# 2x8_GPIO_board.net
KiCad netlist of a schematic drawn in EAGLE
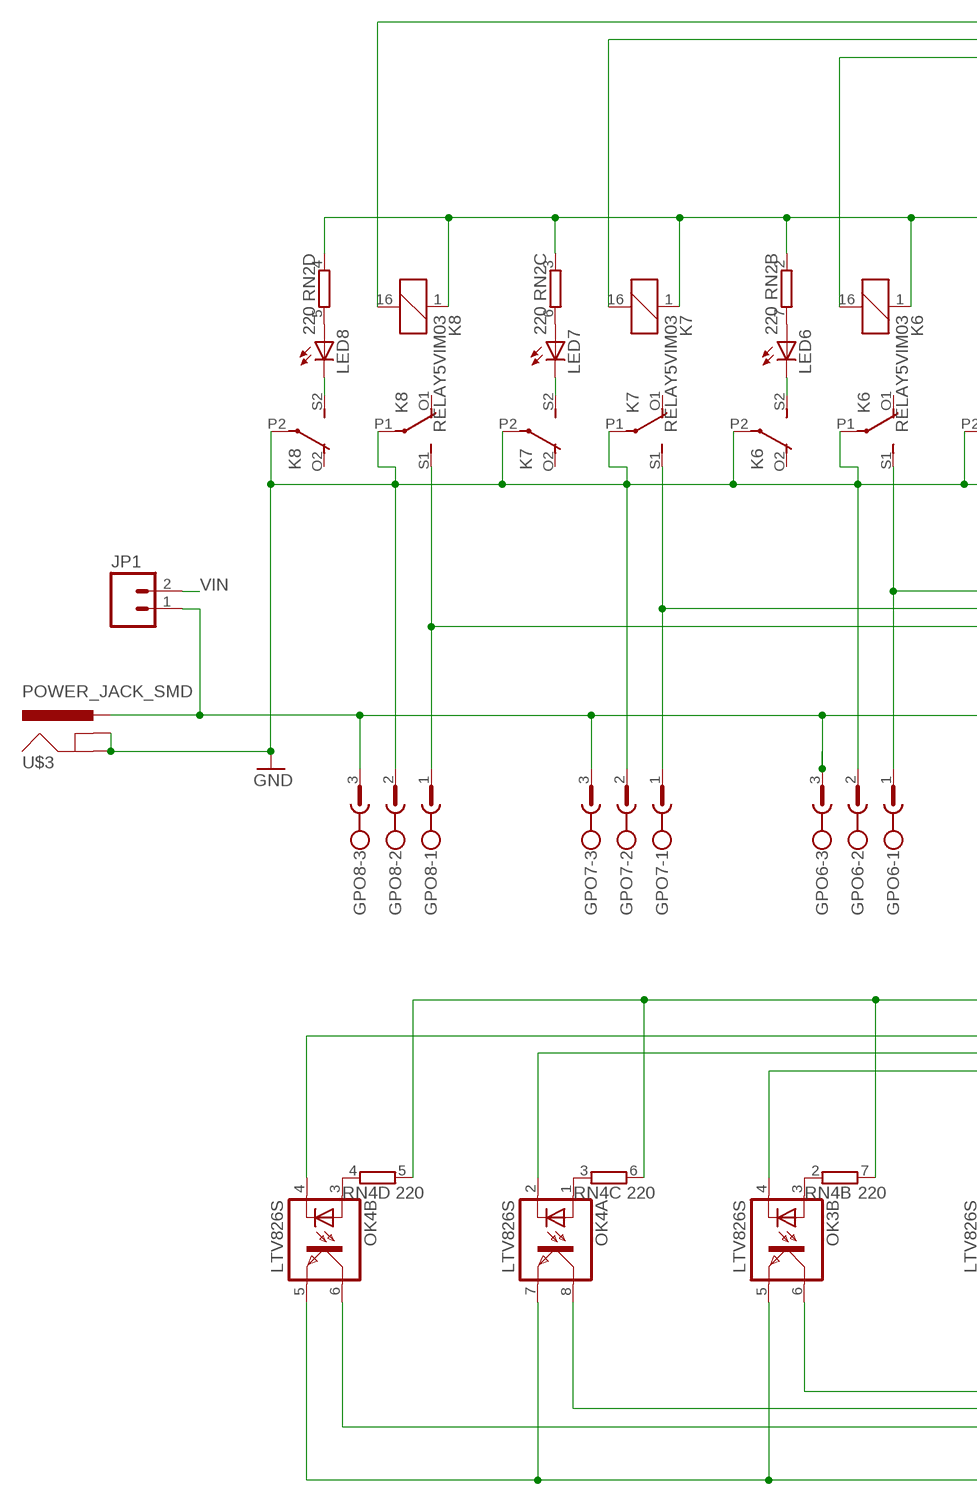
[diagram p0: schematic, sheet 1, part 1 of 2]
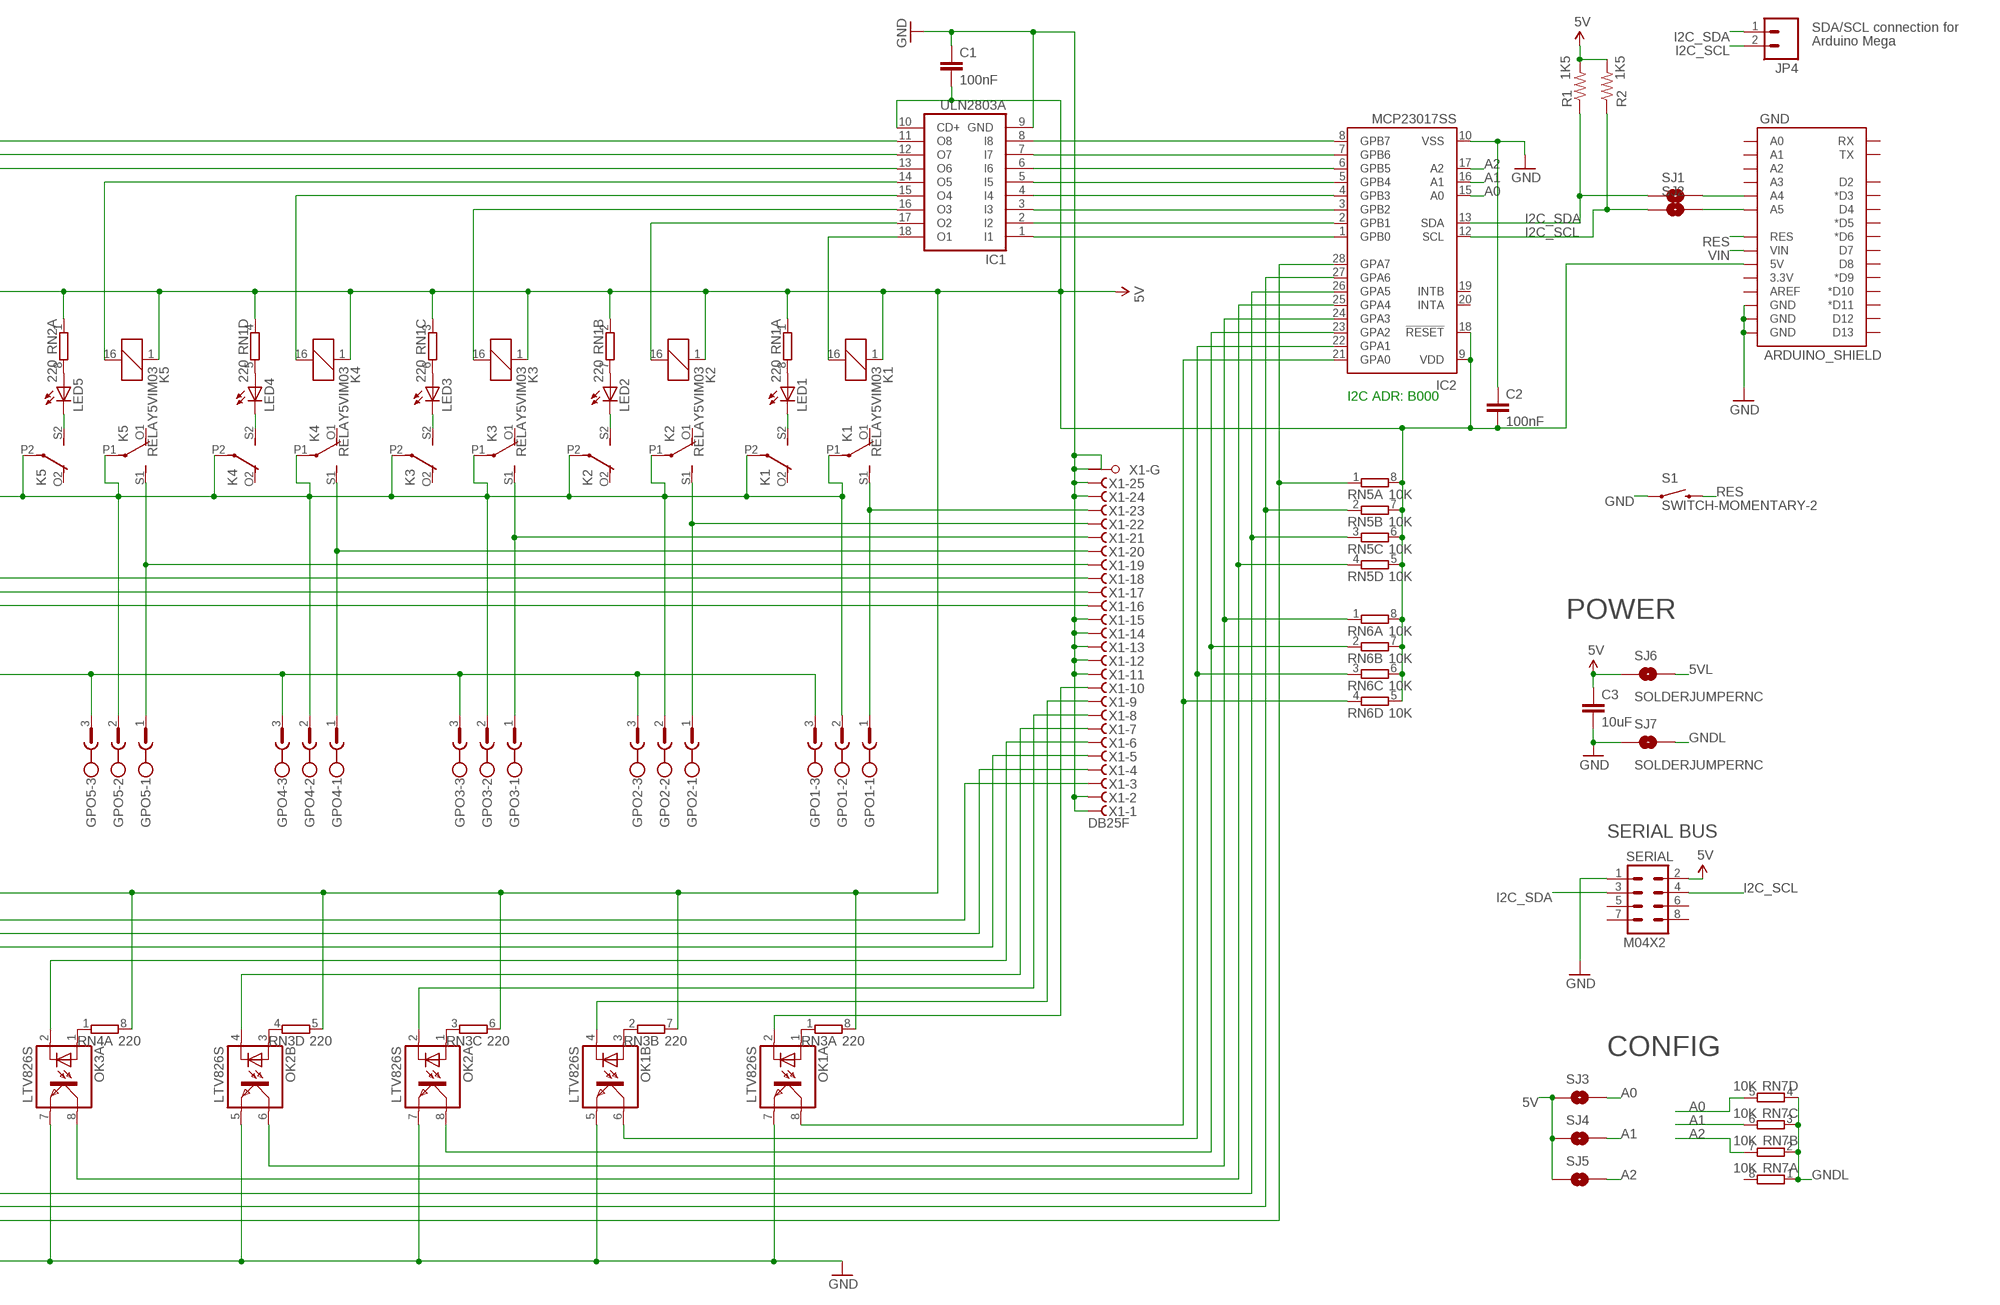
[diagram p1: schematic, sheet 1, part 2 of 2]

(export (version "E")
  (design (tool "Eeschema 10.0.6"))
  (components
    (comp (ref "C1")
      (value "100nF")
      (footprint "eagle-import:0805")
      (libsource (lib "eagle-import") (part "CAP0805"))
    )
    (comp (ref "C2")
      (value "100nF")
      (footprint "eagle-import:0603-CAP")
      (libsource (lib "eagle-import") (part "CAP0603-CAP"))
    )
    (comp (ref "C3")
      (value "10uF")
      (footprint "eagle-import:0805")
      (libsource (lib "eagle-import") (part "CAP0805"))
    )
    (comp (ref "GND")
      (value "ARDUINO_SHIELD")
      (footprint "eagle-import:ARDUINO_BOXSHIELD_NOHOLES")
      (libsource (lib "eagle-import") (part "ARDUINO_SHIELD"))
    )
    (comp (ref "GPO1")
      (value "CON1")
      (footprint "eagle-import:MSTBV3")
      (fields (field (name "MPN") "MSTBV 2,5/3-GF-5.08"))
      (libsource (lib "eagle-import") (part "MSTBV3"))
    )
    (comp (ref "GPO2")
      (value "CON1")
      (footprint "eagle-import:MSTBV3")
      (fields (field (name "MPN") "MSTBV 2,5/3-GF-5.08"))
      (libsource (lib "eagle-import") (part "MSTBV3"))
    )
    (comp (ref "GPO3")
      (value "CON1")
      (footprint "eagle-import:MSTBV3")
      (fields (field (name "MPN") "MSTBV 2,5/3-GF-5.08"))
      (libsource (lib "eagle-import") (part "MSTBV3"))
    )
    (comp (ref "GPO4")
      (value "CON1")
      (footprint "eagle-import:MSTBV3")
      (fields (field (name "MPN") "MSTBV 2,5/3-GF-5.08"))
      (libsource (lib "eagle-import") (part "MSTBV3"))
    )
    (comp (ref "GPO5")
      (value "CON1")
      (footprint "eagle-import:MSTBV3")
      (fields (field (name "MPN") "MSTBV 2,5/3-GF-5.08"))
      (libsource (lib "eagle-import") (part "MSTBV3"))
    )
    (comp (ref "GPO6")
      (value "CON1")
      (footprint "eagle-import:MSTBV3")
      (fields (field (name "MPN") "MSTBV 2,5/3-GF-5.08"))
      (libsource (lib "eagle-import") (part "MSTBV3"))
    )
    (comp (ref "GPO7")
      (value "CON1")
      (footprint "eagle-import:MSTBV3")
      (fields (field (name "MPN") "MSTBV 2,5/3-GF-5.08"))
      (libsource (lib "eagle-import") (part "MSTBV3"))
    )
    (comp (ref "GPO8")
      (value "GPO8")
      (footprint "eagle-import:MSTBV3")
      (fields (field (name "MPN") "MSTBV 2,5/3-GF-5.08"))
      (libsource (lib "eagle-import") (part "MSTBV3"))
    )
    (comp (ref "IC1")
      (value "ULN2803A")
      (footprint "eagle-import:SO18W")
      (libsource (lib "eagle-import") (part "ULN2803ASO18W"))
    )
    (comp (ref "IC2")
      (value "MCP23017SS")
      (footprint "eagle-import:SSOP28")
      (fields (field (name "MF") "MICROCHIP") (field (name "MPN") "MCP23017-E/SS"))
      (libsource (lib "eagle-import") (part "MCP23017SS"))
    )
    (comp (ref "JP1")
      (value "M02LOCK")
      (footprint "eagle-import:1X02_LOCK")
      (libsource (lib "eagle-import") (part "M02LOCK"))
    )
    (comp (ref "JP4")
      (value "M02PTH")
      (footprint "eagle-import:1X02")
      (libsource (lib "eagle-import") (part "M02PTH"))
    )
    (comp (ref "K1")
      (value "RELAY5VIM03")
      (footprint "eagle-import:DS2Y")
      (libsource (lib "eagle-import") (part "RELAY5VIM03"))
    )
    (comp (ref "K2")
      (value "RELAY5VIM03")
      (footprint "eagle-import:DS2Y")
      (libsource (lib "eagle-import") (part "RELAY5VIM03"))
    )
    (comp (ref "K3")
      (value "RELAY5VIM03")
      (footprint "eagle-import:DS2Y")
      (libsource (lib "eagle-import") (part "RELAY5VIM03"))
    )
    (comp (ref "K4")
      (value "RELAY5VIM03")
      (footprint "eagle-import:DS2Y")
      (libsource (lib "eagle-import") (part "RELAY5VIM03"))
    )
    (comp (ref "K5")
      (value "RELAY5VIM03")
      (footprint "eagle-import:DS2Y")
      (libsource (lib "eagle-import") (part "RELAY5VIM03"))
    )
    (comp (ref "K6")
      (value "RELAY5VIM03")
      (footprint "eagle-import:DS2Y")
      (libsource (lib "eagle-import") (part "RELAY5VIM03"))
    )
    (comp (ref "K7")
      (value "RELAY5VIM03")
      (footprint "eagle-import:DS2Y")
      (libsource (lib "eagle-import") (part "RELAY5VIM03"))
    )
    (comp (ref "K8")
      (value "RELAY5VIM03")
      (footprint "eagle-import:DS2Y")
      (libsource (lib "eagle-import") (part "RELAY5VIM03"))
    )
    (comp (ref "LED1")
      (value "LED0603")
      (footprint "eagle-import:LED-0603")
      (libsource (lib "eagle-import") (part "LED0603"))
    )
    (comp (ref "LED2")
      (value "LED0603")
      (footprint "eagle-import:LED-0603")
      (libsource (lib "eagle-import") (part "LED0603"))
    )
    (comp (ref "LED3")
      (value "LED0603")
      (footprint "eagle-import:LED-0603")
      (libsource (lib "eagle-import") (part "LED0603"))
    )
    (comp (ref "LED4")
      (value "LED0603")
      (footprint "eagle-import:LED-0603")
      (libsource (lib "eagle-import") (part "LED0603"))
    )
    (comp (ref "LED5")
      (value "LED0603")
      (footprint "eagle-import:LED-0603")
      (libsource (lib "eagle-import") (part "LED0603"))
    )
    (comp (ref "LED6")
      (value "LED0603")
      (footprint "eagle-import:LED-0603")
      (libsource (lib "eagle-import") (part "LED0603"))
    )
    (comp (ref "LED7")
      (value "LED0603")
      (footprint "eagle-import:LED-0603")
      (libsource (lib "eagle-import") (part "LED0603"))
    )
    (comp (ref "LED8")
      (value "LED0603")
      (footprint "eagle-import:LED-0603")
      (libsource (lib "eagle-import") (part "LED0603"))
    )
    (comp (ref "OK1")
      (value "LTV826S")
      (footprint "eagle-import:DIL8-SMD")
      (libsource (lib "eagle-import") (part "LTV826S"))
    )
    (comp (ref "OK2")
      (value "LTV826S")
      (footprint "eagle-import:DIL8-SMD")
      (libsource (lib "eagle-import") (part "LTV826S"))
    )
    (comp (ref "OK3")
      (value "LTV826S")
      (footprint "eagle-import:DIL8-SMD")
      (libsource (lib "eagle-import") (part "LTV826S"))
    )
    (comp (ref "OK4")
      (value "LTV826S")
      (footprint "eagle-import:DIL8-SMD")
      (libsource (lib "eagle-import") (part "LTV826S"))
    )
    (comp (ref "R1")
      (value "1K5")
      (footprint "eagle-import:0603-RES")
      (libsource (lib "eagle-import") (part "RESISTOR0603-RES"))
    )
    (comp (ref "R2")
      (value "1K5")
      (footprint "eagle-import:0603-RES")
      (libsource (lib "eagle-import") (part "RESISTOR0603-RES"))
    )
    (comp (ref "RN1")
      (value "220")
      (footprint "eagle-import:CAY16")
      (libsource (lib "eagle-import") (part "resistor-dil_4R-NCAY16"))
    )
    (comp (ref "RN2")
      (value "220")
      (footprint "eagle-import:CAY16")
      (libsource (lib "eagle-import") (part "resistor-dil_4R-NCAY16"))
    )
    (comp (ref "RN3")
      (value "220")
      (footprint "eagle-import:CAY16")
      (libsource (lib "eagle-import") (part "resistor-dil_4R-NCAY16"))
    )
    (comp (ref "RN4")
      (value "220")
      (footprint "eagle-import:CAY16")
      (libsource (lib "eagle-import") (part "resistor-dil_4R-NCAY16"))
    )
    (comp (ref "RN5")
      (value "10K")
      (footprint "eagle-import:CAY16")
      (libsource (lib "eagle-import") (part "resistor-dil_4R-NCAY16"))
    )
    (comp (ref "RN6")
      (value "10K")
      (footprint "eagle-import:CAY16")
      (libsource (lib "eagle-import") (part "resistor-dil_4R-NCAY16"))
    )
    (comp (ref "RN7")
      (value "10K")
      (footprint "eagle-import:CAY16_HAND")
      (libsource (lib "eagle-import") (part "4R-NCAY16"))
    )
    (comp (ref "S1")
      (value "SWITCH-MOMENTARY-2")
      (footprint "eagle-import:TACTILE_SWITCH_TALL")
      (libsource (lib "eagle-import") (part "SWITCH-MOMENTARY-2"))
    )
    (comp (ref "SERIAL")
      (value "M04X2")
      (footprint "eagle-import:2X4")
      (libsource (lib "eagle-import") (part "M04X2"))
    )
    (comp (ref "SJ1")
      (value "SOLDERJUMPERNC")
      (footprint "eagle-import:SJ_2S")
      (libsource (lib "eagle-import") (part "SOLDERJUMPERNC"))
    )
    (comp (ref "SJ2")
      (value "SOLDERJUMPERNC")
      (footprint "eagle-import:SJ_2S")
      (libsource (lib "eagle-import") (part "SOLDERJUMPERNC"))
    )
    (comp (ref "SJ3")
      (value "SOLDERJUMPERNC")
      (footprint "eagle-import:SJ_2S")
      (libsource (lib "eagle-import") (part "SOLDERJUMPERNC"))
    )
    (comp (ref "SJ4")
      (value "SOLDERJUMPERNC")
      (footprint "eagle-import:SJ_2S")
      (libsource (lib "eagle-import") (part "SOLDERJUMPERNC"))
    )
    (comp (ref "SJ5")
      (value "SOLDERJUMPERNC")
      (footprint "eagle-import:SJ_2S")
      (libsource (lib "eagle-import") (part "SOLDERJUMPERNC"))
    )
    (comp (ref "SJ6")
      (value "SOLDERJUMPERNC")
      (footprint "eagle-import:SJ_2S")
      (libsource (lib "eagle-import") (part "SOLDERJUMPERNC"))
    )
    (comp (ref "SJ7")
      (value "SOLDERJUMPERNC")
      (footprint "eagle-import:SJ_2S")
      (libsource (lib "eagle-import") (part "SOLDERJUMPERNC"))
    )
    (comp (ref "U$3")
      (value "POWER_JACK_SMD")
      (footprint "eagle-import:POWER_JACK_SMD")
      (libsource (lib "eagle-import") (part "POWER_JACK_SMD"))
    )
    (comp (ref "X1")
      (value "DB25F")
      (footprint "eagle-import:F25HP")
      (libsource (lib "eagle-import") (part "F25HPS"))
    )
  )
  (nets
    (net (code "1") (name "/5VL") (class "Default")
      (node (ref "SJ6") (pin "2") (pinfunction "2_2") (pintype "passive"))
    )
    (net (code "2") (name "/A0") (class "Default")
      (node (ref "IC2") (pin "15") (pinfunction "A0_15") (pintype "input"))
      (node (ref "RN7") (pin "5") (pinfunction "2_5") (pintype "passive"))
      (node (ref "SJ3") (pin "2") (pinfunction "2_2") (pintype "passive"))
    )
    (net (code "3") (name "/A1") (class "Default")
      (node (ref "IC2") (pin "16") (pinfunction "A1_16") (pintype "input"))
      (node (ref "RN7") (pin "6") (pinfunction "2_6") (pintype "passive"))
      (node (ref "SJ4") (pin "2") (pinfunction "2_2") (pintype "passive"))
    )
    (net (code "4") (name "/A2") (class "Default")
      (node (ref "IC2") (pin "17") (pinfunction "A2_17") (pintype "input"))
      (node (ref "RN7") (pin "7") (pinfunction "2_7") (pintype "passive"))
      (node (ref "SJ5") (pin "2") (pinfunction "2_2") (pintype "passive"))
    )
    (net (code "5") (name "/GNDL") (class "Default")
      (node (ref "RN7") (pin "1") (pinfunction "1_1") (pintype "passive"))
      (node (ref "RN7") (pin "2") (pinfunction "1_2") (pintype "passive"))
      (node (ref "RN7") (pin "3") (pinfunction "1_3") (pintype "passive"))
      (node (ref "RN7") (pin "4") (pinfunction "1_4") (pintype "passive"))
      (node (ref "SJ7") (pin "2") (pinfunction "2_2") (pintype "passive"))
    )
    (net (code "6") (name "/I2C_SCL") (class "Default")
      (node (ref "IC2") (pin "12") (pinfunction "SCL_12") (pintype "input"))
      (node (ref "JP4") (pin "2") (pinfunction "2_2") (pintype "passive"))
      (node (ref "R2") (pin "1") (pinfunction "1_1") (pintype "passive"))
      (node (ref "SERIAL") (pin "4") (pinfunction "4_4") (pintype "passive"))
      (node (ref "SJ2") (pin "1") (pinfunction "1_1") (pintype "passive"))
    )
    (net (code "7") (name "/I2C_SDA") (class "Default")
      (node (ref "IC2") (pin "13") (pinfunction "SDA_13") (pintype "bidirectional"))
      (node (ref "JP4") (pin "1") (pinfunction "1_1") (pintype "passive"))
      (node (ref "R1") (pin "1") (pinfunction "1_1") (pintype "passive"))
      (node (ref "SERIAL") (pin "3") (pinfunction "3_3") (pintype "passive"))
      (node (ref "SJ1") (pin "1") (pinfunction "1_1") (pintype "passive"))
    )
    (net (code "8") (name "/RES") (class "Default")
      (node (ref "GND") (pin "RESET") (pinfunction "RES_RESET") (pintype "bidirectional"))
      (node (ref "S1") (pin "B2") (pinfunction "2_B2") (pintype "passive"))
    )
    (net (code "9") (name "/VIN") (class "Default")
      (node (ref "GND") (pin "VIN") (pinfunction "VIN_VIN") (pintype "bidirectional"))
      (node (ref "JP1") (pin "2") (pinfunction "2_2") (pintype "passive"))
    )
    (net (code "10") (name "5V") (class "Default")
      (node (ref "C1") (pin "2") (pinfunction "2_2") (pintype "passive"))
      (node (ref "C2") (pin "2") (pinfunction "2_2") (pintype "passive"))
      (node (ref "C3") (pin "1") (pinfunction "1_1") (pintype "passive"))
      (node (ref "GND") (pin "5V@0") (pinfunction "5V_5V@0") (pintype "bidirectional"))
      (node (ref "IC1") (pin "10") (pinfunction "CD+_10") (pintype "passive"))
      (node (ref "IC2") (pin "18") (pinfunction "~{RESET}_18") (pintype "input"))
      (node (ref "IC2") (pin "9") (pinfunction "VDD_9") (pintype "power_in"))
      (node (ref "K1") (pin "1") (pinfunction "1_1") (pintype "passive"))
      (node (ref "K2") (pin "1") (pinfunction "1_1") (pintype "passive"))
      (node (ref "K3") (pin "1") (pinfunction "1_1") (pintype "passive"))
      (node (ref "K4") (pin "1") (pinfunction "1_1") (pintype "passive"))
      (node (ref "K5") (pin "1") (pinfunction "1_1") (pintype "passive"))
      (node (ref "K6") (pin "1") (pinfunction "1_1") (pintype "passive"))
      (node (ref "K7") (pin "1") (pinfunction "1_1") (pintype "passive"))
      (node (ref "K8") (pin "1") (pinfunction "1_1") (pintype "passive"))
      (node (ref "R1") (pin "2") (pinfunction "2_2") (pintype "passive"))
      (node (ref "R2") (pin "2") (pinfunction "2_2") (pintype "passive"))
      (node (ref "RN1") (pin "1") (pinfunction "1_1") (pintype "passive"))
      (node (ref "RN1") (pin "2") (pinfunction "1_2") (pintype "passive"))
      (node (ref "RN1") (pin "3") (pinfunction "1_3") (pintype "passive"))
      (node (ref "RN1") (pin "4") (pinfunction "1_4") (pintype "passive"))
      (node (ref "RN2") (pin "1") (pinfunction "1_1") (pintype "passive"))
      (node (ref "RN2") (pin "2") (pinfunction "1_2") (pintype "passive"))
      (node (ref "RN2") (pin "3") (pinfunction "1_3") (pintype "passive"))
      (node (ref "RN2") (pin "4") (pinfunction "1_4") (pintype "passive"))
      (node (ref "RN3") (pin "5") (pinfunction "2_5") (pintype "passive"))
      (node (ref "RN3") (pin "6") (pinfunction "2_6") (pintype "passive"))
      (node (ref "RN3") (pin "7") (pinfunction "2_7") (pintype "passive"))
      (node (ref "RN3") (pin "8") (pinfunction "2_8") (pintype "passive"))
      (node (ref "RN4") (pin "5") (pinfunction "2_5") (pintype "passive"))
      (node (ref "RN4") (pin "6") (pinfunction "2_6") (pintype "passive"))
      (node (ref "RN4") (pin "7") (pinfunction "2_7") (pintype "passive"))
      (node (ref "RN4") (pin "8") (pinfunction "2_8") (pintype "passive"))
      (node (ref "RN5") (pin "5") (pinfunction "2_5") (pintype "passive"))
      (node (ref "RN5") (pin "6") (pinfunction "2_6") (pintype "passive"))
      (node (ref "RN5") (pin "7") (pinfunction "2_7") (pintype "passive"))
      (node (ref "RN5") (pin "8") (pinfunction "2_8") (pintype "passive"))
      (node (ref "RN6") (pin "5") (pinfunction "2_5") (pintype "passive"))
      (node (ref "RN6") (pin "6") (pinfunction "2_6") (pintype "passive"))
      (node (ref "RN6") (pin "7") (pinfunction "2_7") (pintype "passive"))
      (node (ref "RN6") (pin "8") (pinfunction "2_8") (pintype "passive"))
      (node (ref "SERIAL") (pin "2") (pinfunction "2_2") (pintype "passive"))
      (node (ref "SJ3") (pin "1") (pinfunction "1_1") (pintype "passive"))
      (node (ref "SJ4") (pin "1") (pinfunction "1_1") (pintype "passive"))
      (node (ref "SJ5") (pin "1") (pinfunction "1_1") (pintype "passive"))
      (node (ref "SJ6") (pin "1") (pinfunction "1_1") (pintype "passive"))
    )
    (net (code "11") (name "GND") (class "Default")
      (node (ref "C1") (pin "1") (pinfunction "1_1") (pintype "passive"))
      (node (ref "C2") (pin "1") (pinfunction "1_1") (pintype "passive"))
      (node (ref "C3") (pin "2") (pinfunction "2_2") (pintype "passive"))
      (node (ref "GND") (pin "GND@0") (pinfunction "GND_GND@0") (pintype "bidirectional"))
      (node (ref "GND") (pin "GND@1") (pinfunction "GND_GND@1") (pintype "bidirectional"))
      (node (ref "GND") (pin "GND@4") (pinfunction "GND_GND@4") (pintype "bidirectional"))
      (node (ref "GPO1") (pin "2") (pinfunction "1_2") (pintype "passive"))
      (node (ref "GPO2") (pin "2") (pinfunction "1_2") (pintype "passive"))
      (node (ref "GPO3") (pin "2") (pinfunction "1_2") (pintype "passive"))
      (node (ref "GPO4") (pin "2") (pinfunction "1_2") (pintype "passive"))
      (node (ref "GPO5") (pin "2") (pinfunction "1_2") (pintype "passive"))
      (node (ref "GPO6") (pin "2") (pinfunction "1_2") (pintype "passive"))
      (node (ref "GPO7") (pin "2") (pinfunction "1_2") (pintype "passive"))
      (node (ref "GPO8") (pin "2") (pinfunction "1_2") (pintype "passive"))
      (node (ref "IC1") (pin "9") (pinfunction "GND_9") (pintype "power_in"))
      (node (ref "IC2") (pin "10") (pinfunction "VSS_10") (pintype "power_in"))
      (node (ref "K1") (pin "P1") (pinfunction "P_P1") (pintype "passive"))
      (node (ref "K1") (pin "P2") (pinfunction "P_P2") (pintype "passive"))
      (node (ref "K2") (pin "P1") (pinfunction "P_P1") (pintype "passive"))
      (node (ref "K2") (pin "P2") (pinfunction "P_P2") (pintype "passive"))
      (node (ref "K3") (pin "P1") (pinfunction "P_P1") (pintype "passive"))
      (node (ref "K3") (pin "P2") (pinfunction "P_P2") (pintype "passive"))
      (node (ref "K4") (pin "P1") (pinfunction "P_P1") (pintype "passive"))
      (node (ref "K4") (pin "P2") (pinfunction "P_P2") (pintype "passive"))
      (node (ref "K5") (pin "P1") (pinfunction "P_P1") (pintype "passive"))
      (node (ref "K5") (pin "P2") (pinfunction "P_P2") (pintype "passive"))
      (node (ref "K6") (pin "P1") (pinfunction "P_P1") (pintype "passive"))
      (node (ref "K6") (pin "P2") (pinfunction "P_P2") (pintype "passive"))
      (node (ref "K7") (pin "P1") (pinfunction "P_P1") (pintype "passive"))
      (node (ref "K7") (pin "P2") (pinfunction "P_P2") (pintype "passive"))
      (node (ref "K8") (pin "P1") (pinfunction "P_P1") (pintype "passive"))
      (node (ref "K8") (pin "P2") (pinfunction "P_P2") (pintype "passive"))
      (node (ref "OK1") (pin "5") (pinfunction "EMIT_5") (pintype "passive"))
      (node (ref "OK1") (pin "7") (pinfunction "EMIT_7") (pintype "passive"))
      (node (ref "OK2") (pin "5") (pinfunction "EMIT_5") (pintype "passive"))
      (node (ref "OK2") (pin "7") (pinfunction "EMIT_7") (pintype "passive"))
      (node (ref "OK3") (pin "5") (pinfunction "EMIT_5") (pintype "passive"))
      (node (ref "OK3") (pin "7") (pinfunction "EMIT_7") (pintype "passive"))
      (node (ref "OK4") (pin "5") (pinfunction "EMIT_5") (pintype "passive"))
      (node (ref "OK4") (pin "7") (pinfunction "EMIT_7") (pintype "passive"))
      (node (ref "S1") (pin "A2") (pinfunction "1_A2") (pintype "passive"))
      (node (ref "SERIAL") (pin "1") (pinfunction "1_1") (pintype "passive"))
      (node (ref "SJ7") (pin "1") (pinfunction "1_1") (pintype "passive"))
      (node (ref "U$3") (pin "GND") (pinfunction "GND_GND") (pintype "bidirectional"))
      (node (ref "U$3") (pin "SHUNT") (pinfunction "GNDBREAK_SHUNT") (pintype "bidirectional"))
      (node (ref "X1") (pin "1") (pinfunction "F_1") (pintype "passive"))
      (node (ref "X1") (pin "11") (pinfunction "F_11") (pintype "passive"))
      (node (ref "X1") (pin "12") (pinfunction "F_12") (pintype "passive"))
      (node (ref "X1") (pin "13") (pinfunction "F_13") (pintype "passive"))
      (node (ref "X1") (pin "14") (pinfunction "F_14") (pintype "passive"))
      (node (ref "X1") (pin "15") (pinfunction "F_15") (pintype "passive"))
      (node (ref "X1") (pin "2") (pinfunction "F_2") (pintype "passive"))
      (node (ref "X1") (pin "24") (pinfunction "F_24") (pintype "passive"))
      (node (ref "X1") (pin "25") (pinfunction "F_25") (pintype "passive"))
      (node (ref "X1") (pin "G1") (pinfunction "G1_G1") (pintype "passive"))
      (node (ref "X1") (pin "G2") (pinfunction "G2_G2") (pintype "passive"))
    )
    (net (code "12") (name "Net-(GND-PadA4)") (class "Default")
      (node (ref "GND") (pin "A4") (pinfunction "A4_A4") (pintype "bidirectional"))
      (node (ref "SJ1") (pin "2") (pinfunction "2_2") (pintype "passive"))
    )
    (net (code "13") (name "Net-(GND-PadA5)") (class "Default")
      (node (ref "GND") (pin "A5") (pinfunction "A5_A5") (pintype "bidirectional"))
      (node (ref "SJ2") (pin "2") (pinfunction "2_2") (pintype "passive"))
    )
    (net (code "14") (name "Net-(GPO1C-1)") (class "Default")
      (node (ref "GPO1") (pin "3") (pinfunction "1_3") (pintype "passive"))
      (node (ref "GPO2") (pin "3") (pinfunction "1_3") (pintype "passive"))
      (node (ref "GPO3") (pin "3") (pinfunction "1_3") (pintype "passive"))
      (node (ref "GPO4") (pin "3") (pinfunction "1_3") (pintype "passive"))
      (node (ref "GPO5") (pin "3") (pinfunction "1_3") (pintype "passive"))
      (node (ref "GPO6") (pin "3") (pinfunction "1_3") (pintype "passive"))
      (node (ref "GPO7") (pin "3") (pinfunction "1_3") (pintype "passive"))
      (node (ref "GPO8") (pin "3") (pinfunction "1_3") (pintype "passive"))
      (node (ref "JP1") (pin "1") (pinfunction "1_1") (pintype "passive"))
      (node (ref "U$3") (pin "PWR") (pinfunction "PWR_PWR") (pintype "bidirectional"))
    )
    (net (code "15") (name "Net-(IC1-I1)") (class "Default")
      (node (ref "IC1") (pin "1") (pinfunction "I1_1") (pintype "input"))
      (node (ref "IC2") (pin "1") (pinfunction "GPB0_1") (pintype "bidirectional"))
    )
    (net (code "16") (name "Net-(IC1-I2)") (class "Default")
      (node (ref "IC1") (pin "2") (pinfunction "I2_2") (pintype "input"))
      (node (ref "IC2") (pin "2") (pinfunction "GPB1_2") (pintype "bidirectional"))
    )
    (net (code "17") (name "Net-(IC1-I3)") (class "Default")
      (node (ref "IC1") (pin "3") (pinfunction "I3_3") (pintype "input"))
      (node (ref "IC2") (pin "3") (pinfunction "GPB2_3") (pintype "bidirectional"))
    )
    (net (code "18") (name "Net-(IC1-I4)") (class "Default")
      (node (ref "IC1") (pin "4") (pinfunction "I4_4") (pintype "input"))
      (node (ref "IC2") (pin "4") (pinfunction "GPB3_4") (pintype "bidirectional"))
    )
    (net (code "19") (name "Net-(IC1-I5)") (class "Default")
      (node (ref "IC1") (pin "5") (pinfunction "I5_5") (pintype "input"))
      (node (ref "IC2") (pin "5") (pinfunction "GPB4_5") (pintype "bidirectional"))
    )
    (net (code "20") (name "Net-(IC1-I6)") (class "Default")
      (node (ref "IC1") (pin "6") (pinfunction "I6_6") (pintype "input"))
      (node (ref "IC2") (pin "6") (pinfunction "GPB5_6") (pintype "bidirectional"))
    )
    (net (code "21") (name "Net-(IC1-I7)") (class "Default")
      (node (ref "IC1") (pin "7") (pinfunction "I7_7") (pintype "input"))
      (node (ref "IC2") (pin "7") (pinfunction "GPB6_7") (pintype "bidirectional"))
    )
    (net (code "22") (name "Net-(IC1-I8)") (class "Default")
      (node (ref "IC1") (pin "8") (pinfunction "I8_8") (pintype "input"))
      (node (ref "IC2") (pin "8") (pinfunction "GPB7_8") (pintype "bidirectional"))
    )
    (net (code "23") (name "Net-(IC1-O1)") (class "Default")
      (node (ref "IC1") (pin "18") (pinfunction "O1_18") (pintype "open_collector"))
      (node (ref "K1") (pin "16") (pinfunction "2_16") (pintype "passive"))
    )
    (net (code "24") (name "Net-(IC1-O2)") (class "Default")
      (node (ref "IC1") (pin "17") (pinfunction "O2_17") (pintype "open_collector"))
      (node (ref "K2") (pin "16") (pinfunction "2_16") (pintype "passive"))
    )
    (net (code "25") (name "Net-(IC1-O3)") (class "Default")
      (node (ref "IC1") (pin "16") (pinfunction "O3_16") (pintype "open_collector"))
      (node (ref "K3") (pin "16") (pinfunction "2_16") (pintype "passive"))
    )
    (net (code "26") (name "Net-(IC1-O4)") (class "Default")
      (node (ref "IC1") (pin "15") (pinfunction "O4_15") (pintype "open_collector"))
      (node (ref "K4") (pin "16") (pinfunction "2_16") (pintype "passive"))
    )
    (net (code "27") (name "Net-(IC1-O5)") (class "Default")
      (node (ref "IC1") (pin "14") (pinfunction "O5_14") (pintype "open_collector"))
      (node (ref "K5") (pin "16") (pinfunction "2_16") (pintype "passive"))
    )
    (net (code "28") (name "Net-(IC1-O6)") (class "Default")
      (node (ref "IC1") (pin "13") (pinfunction "O6_13") (pintype "open_collector"))
      (node (ref "K6") (pin "16") (pinfunction "2_16") (pintype "passive"))
    )
    (net (code "29") (name "Net-(IC1-O7)") (class "Default")
      (node (ref "IC1") (pin "12") (pinfunction "O7_12") (pintype "open_collector"))
      (node (ref "K7") (pin "16") (pinfunction "2_16") (pintype "passive"))
    )
    (net (code "30") (name "Net-(IC1-O8)") (class "Default")
      (node (ref "IC1") (pin "11") (pinfunction "O8_11") (pintype "open_collector"))
      (node (ref "K8") (pin "16") (pinfunction "2_16") (pintype "passive"))
    )
    (net (code "31") (name "Net-(IC2-GPA0)") (class "Default")
      (node (ref "IC2") (pin "21") (pinfunction "GPA0_21") (pintype "bidirectional"))
      (node (ref "OK1") (pin "8") (pinfunction "COL_8") (pintype "passive"))
      (node (ref "RN6") (pin "4") (pinfunction "1_4") (pintype "passive"))
    )
    (net (code "32") (name "Net-(IC2-GPA1)") (class "Default")
      (node (ref "IC2") (pin "22") (pinfunction "GPA1_22") (pintype "bidirectional"))
      (node (ref "OK1") (pin "6") (pinfunction "COL_6") (pintype "passive"))
      (node (ref "RN6") (pin "3") (pinfunction "1_3") (pintype "passive"))
    )
    (net (code "33") (name "Net-(IC2-GPA2)") (class "Default")
      (node (ref "IC2") (pin "23") (pinfunction "GPA2_23") (pintype "bidirectional"))
      (node (ref "OK2") (pin "8") (pinfunction "COL_8") (pintype "passive"))
      (node (ref "RN6") (pin "2") (pinfunction "1_2") (pintype "passive"))
    )
    (net (code "34") (name "Net-(IC2-GPA3)") (class "Default")
      (node (ref "IC2") (pin "24") (pinfunction "GPA3_24") (pintype "bidirectional"))
      (node (ref "OK2") (pin "6") (pinfunction "COL_6") (pintype "passive"))
      (node (ref "RN6") (pin "1") (pinfunction "1_1") (pintype "passive"))
    )
    (net (code "35") (name "Net-(IC2-GPA4)") (class "Default")
      (node (ref "IC2") (pin "25") (pinfunction "GPA4_25") (pintype "bidirectional"))
      (node (ref "OK3") (pin "8") (pinfunction "COL_8") (pintype "passive"))
      (node (ref "RN5") (pin "4") (pinfunction "1_4") (pintype "passive"))
    )
    (net (code "36") (name "Net-(IC2-GPA5)") (class "Default")
      (node (ref "IC2") (pin "26") (pinfunction "GPA5_26") (pintype "bidirectional"))
      (node (ref "OK3") (pin "6") (pinfunction "COL_6") (pintype "passive"))
      (node (ref "RN5") (pin "3") (pinfunction "1_3") (pintype "passive"))
    )
    (net (code "37") (name "Net-(IC2-GPA6)") (class "Default")
      (node (ref "IC2") (pin "27") (pinfunction "GPA6_27") (pintype "bidirectional"))
      (node (ref "OK4") (pin "8") (pinfunction "COL_8") (pintype "passive"))
      (node (ref "RN5") (pin "2") (pinfunction "1_2") (pintype "passive"))
    )
    (net (code "38") (name "Net-(IC2-GPA7)") (class "Default")
      (node (ref "IC2") (pin "28") (pinfunction "GPA7_28") (pintype "bidirectional"))
      (node (ref "OK4") (pin "6") (pinfunction "COL_6") (pintype "passive"))
      (node (ref "RN5") (pin "1") (pinfunction "1_1") (pintype "passive"))
    )
    (net (code "39") (name "Net-(K1B-S)") (class "Default")
      (node (ref "GPO1") (pin "1") (pinfunction "1_1") (pintype "passive"))
      (node (ref "K1") (pin "S1") (pinfunction "S_S1") (pintype "passive"))
      (node (ref "X1") (pin "23") (pinfunction "F_23") (pintype "passive"))
    )
    (net (code "40") (name "Net-(K1C-S)") (class "Default")
      (node (ref "K1") (pin "S2") (pinfunction "S_S2") (pintype "passive"))
      (node (ref "LED1") (pin "C") (pinfunction "C_C") (pintype "passive"))
    )
    (net (code "41") (name "Net-(K2B-S)") (class "Default")
      (node (ref "GPO2") (pin "1") (pinfunction "1_1") (pintype "passive"))
      (node (ref "K2") (pin "S1") (pinfunction "S_S1") (pintype "passive"))
      (node (ref "X1") (pin "22") (pinfunction "F_22") (pintype "passive"))
    )
    (net (code "42") (name "Net-(K2C-S)") (class "Default")
      (node (ref "K2") (pin "S2") (pinfunction "S_S2") (pintype "passive"))
      (node (ref "LED2") (pin "C") (pinfunction "C_C") (pintype "passive"))
    )
    (net (code "43") (name "Net-(K3B-S)") (class "Default")
      (node (ref "GPO3") (pin "1") (pinfunction "1_1") (pintype "passive"))
      (node (ref "K3") (pin "S1") (pinfunction "S_S1") (pintype "passive"))
      (node (ref "X1") (pin "21") (pinfunction "F_21") (pintype "passive"))
    )
    (net (code "44") (name "Net-(K3C-S)") (class "Default")
      (node (ref "K3") (pin "S2") (pinfunction "S_S2") (pintype "passive"))
      (node (ref "LED3") (pin "C") (pinfunction "C_C") (pintype "passive"))
    )
    (net (code "45") (name "Net-(K4B-S)") (class "Default")
      (node (ref "GPO4") (pin "1") (pinfunction "1_1") (pintype "passive"))
      (node (ref "K4") (pin "S1") (pinfunction "S_S1") (pintype "passive"))
      (node (ref "X1") (pin "20") (pinfunction "F_20") (pintype "passive"))
    )
    (net (code "46") (name "Net-(K4C-S)") (class "Default")
      (node (ref "K4") (pin "S2") (pinfunction "S_S2") (pintype "passive"))
      (node (ref "LED4") (pin "C") (pinfunction "C_C") (pintype "passive"))
    )
    (net (code "47") (name "Net-(K5B-S)") (class "Default")
      (node (ref "GPO5") (pin "1") (pinfunction "1_1") (pintype "passive"))
      (node (ref "K5") (pin "S1") (pinfunction "S_S1") (pintype "passive"))
      (node (ref "X1") (pin "19") (pinfunction "F_19") (pintype "passive"))
    )
    (net (code "48") (name "Net-(K5C-S)") (class "Default")
      (node (ref "K5") (pin "S2") (pinfunction "S_S2") (pintype "passive"))
      (node (ref "LED5") (pin "C") (pinfunction "C_C") (pintype "passive"))
    )
    (net (code "49") (name "Net-(K6B-S)") (class "Default")
      (node (ref "GPO6") (pin "1") (pinfunction "1_1") (pintype "passive"))
      (node (ref "K6") (pin "S1") (pinfunction "S_S1") (pintype "passive"))
      (node (ref "X1") (pin "18") (pinfunction "F_18") (pintype "passive"))
    )
    (net (code "50") (name "Net-(K6C-S)") (class "Default")
      (node (ref "K6") (pin "S2") (pinfunction "S_S2") (pintype "passive"))
      (node (ref "LED6") (pin "C") (pinfunction "C_C") (pintype "passive"))
    )
    (net (code "51") (name "Net-(K7B-S)") (class "Default")
      (node (ref "GPO7") (pin "1") (pinfunction "1_1") (pintype "passive"))
      (node (ref "K7") (pin "S1") (pinfunction "S_S1") (pintype "passive"))
      (node (ref "X1") (pin "17") (pinfunction "F_17") (pintype "passive"))
    )
    (net (code "52") (name "Net-(K7C-S)") (class "Default")
      (node (ref "K7") (pin "S2") (pinfunction "S_S2") (pintype "passive"))
      (node (ref "LED7") (pin "C") (pinfunction "C_C") (pintype "passive"))
    )
    (net (code "53") (name "Net-(K8B-S)") (class "Default")
      (node (ref "GPO8") (pin "1") (pinfunction "1_1") (pintype "passive"))
      (node (ref "K8") (pin "S1") (pinfunction "S_S1") (pintype "passive"))
      (node (ref "X1") (pin "16") (pinfunction "F_16") (pintype "passive"))
    )
    (net (code "54") (name "Net-(K8C-S)") (class "Default")
      (node (ref "K8") (pin "S2") (pinfunction "S_S2") (pintype "passive"))
      (node (ref "LED8") (pin "C") (pinfunction "C_C") (pintype "passive"))
    )
    (net (code "55") (name "Net-(OK1A-A)") (class "Default")
      (node (ref "OK1") (pin "1") (pinfunction "A_1") (pintype "passive"))
      (node (ref "RN3") (pin "1") (pinfunction "1_1") (pintype "passive"))
    )
    (net (code "56") (name "Net-(OK1A-C)") (class "Default")
      (node (ref "OK1") (pin "2") (pinfunction "C_2") (pintype "passive"))
      (node (ref "X1") (pin "10") (pinfunction "F_10") (pintype "passive"))
    )
    (net (code "57") (name "Net-(OK1B-A)") (class "Default")
      (node (ref "OK1") (pin "3") (pinfunction "A_3") (pintype "passive"))
      (node (ref "RN3") (pin "2") (pinfunction "1_2") (pintype "passive"))
    )
    (net (code "58") (name "Net-(OK1B-C)") (class "Default")
      (node (ref "OK1") (pin "4") (pinfunction "C_4") (pintype "passive"))
      (node (ref "X1") (pin "9") (pinfunction "F_9") (pintype "passive"))
    )
    (net (code "59") (name "Net-(OK2A-A)") (class "Default")
      (node (ref "OK2") (pin "1") (pinfunction "A_1") (pintype "passive"))
      (node (ref "RN3") (pin "3") (pinfunction "1_3") (pintype "passive"))
    )
    (net (code "60") (name "Net-(OK2A-C)") (class "Default")
      (node (ref "OK2") (pin "2") (pinfunction "C_2") (pintype "passive"))
      (node (ref "X1") (pin "8") (pinfunction "F_8") (pintype "passive"))
    )
    (net (code "61") (name "Net-(OK2B-A)") (class "Default")
      (node (ref "OK2") (pin "3") (pinfunction "A_3") (pintype "passive"))
      (node (ref "RN3") (pin "4") (pinfunction "1_4") (pintype "passive"))
    )
    (net (code "62") (name "Net-(OK2B-C)") (class "Default")
      (node (ref "OK2") (pin "4") (pinfunction "C_4") (pintype "passive"))
      (node (ref "X1") (pin "7") (pinfunction "F_7") (pintype "passive"))
    )
    (net (code "63") (name "Net-(OK3A-A)") (class "Default")
      (node (ref "OK3") (pin "1") (pinfunction "A_1") (pintype "passive"))
      (node (ref "RN4") (pin "1") (pinfunction "1_1") (pintype "passive"))
    )
    (net (code "64") (name "Net-(OK3A-C)") (class "Default")
      (node (ref "OK3") (pin "2") (pinfunction "C_2") (pintype "passive"))
      (node (ref "X1") (pin "6") (pinfunction "F_6") (pintype "passive"))
    )
    (net (code "65") (name "Net-(OK3B-A)") (class "Default")
      (node (ref "OK3") (pin "3") (pinfunction "A_3") (pintype "passive"))
      (node (ref "RN4") (pin "2") (pinfunction "1_2") (pintype "passive"))
    )
    (net (code "66") (name "Net-(OK3B-C)") (class "Default")
      (node (ref "OK3") (pin "4") (pinfunction "C_4") (pintype "passive"))
      (node (ref "X1") (pin "5") (pinfunction "F_5") (pintype "passive"))
    )
    (net (code "67") (name "Net-(OK4A-A)") (class "Default")
      (node (ref "OK4") (pin "1") (pinfunction "A_1") (pintype "passive"))
      (node (ref "RN4") (pin "3") (pinfunction "1_3") (pintype "passive"))
    )
    (net (code "68") (name "Net-(OK4A-C)") (class "Default")
      (node (ref "OK4") (pin "2") (pinfunction "C_2") (pintype "passive"))
      (node (ref "X1") (pin "4") (pinfunction "F_4") (pintype "passive"))
    )
    (net (code "69") (name "Net-(OK4B-A)") (class "Default")
      (node (ref "OK4") (pin "3") (pinfunction "A_3") (pintype "passive"))
      (node (ref "RN4") (pin "4") (pinfunction "1_4") (pintype "passive"))
    )
    (net (code "70") (name "Net-(OK4B-C)") (class "Default")
      (node (ref "OK4") (pin "4") (pinfunction "C_4") (pintype "passive"))
      (node (ref "X1") (pin "3") (pinfunction "F_3") (pintype "passive"))
    )
    (net (code "71") (name "Net-(RN1A-2)") (class "Default")
      (node (ref "LED1") (pin "A") (pinfunction "A_A") (pintype "passive"))
      (node (ref "RN1") (pin "8") (pinfunction "2_8") (pintype "passive"))
    )
    (net (code "72") (name "Net-(RN1B-2)") (class "Default")
      (node (ref "LED2") (pin "A") (pinfunction "A_A") (pintype "passive"))
      (node (ref "RN1") (pin "7") (pinfunction "2_7") (pintype "passive"))
    )
    (net (code "73") (name "Net-(RN1C-2)") (class "Default")
      (node (ref "LED3") (pin "A") (pinfunction "A_A") (pintype "passive"))
      (node (ref "RN1") (pin "6") (pinfunction "2_6") (pintype "passive"))
    )
    (net (code "74") (name "Net-(RN1D-2)") (class "Default")
      (node (ref "LED4") (pin "A") (pinfunction "A_A") (pintype "passive"))
      (node (ref "RN1") (pin "5") (pinfunction "2_5") (pintype "passive"))
    )
    (net (code "75") (name "Net-(RN2A-2)") (class "Default")
      (node (ref "LED5") (pin "A") (pinfunction "A_A") (pintype "passive"))
      (node (ref "RN2") (pin "8") (pinfunction "2_8") (pintype "passive"))
    )
    (net (code "76") (name "Net-(RN2B-2)") (class "Default")
      (node (ref "LED6") (pin "A") (pinfunction "A_A") (pintype "passive"))
      (node (ref "RN2") (pin "7") (pinfunction "2_7") (pintype "passive"))
    )
    (net (code "77") (name "Net-(RN2C-2)") (class "Default")
      (node (ref "LED7") (pin "A") (pinfunction "A_A") (pintype "passive"))
      (node (ref "RN2") (pin "6") (pinfunction "2_6") (pintype "passive"))
    )
    (net (code "78") (name "Net-(RN2D-2)") (class "Default")
      (node (ref "LED8") (pin "A") (pinfunction "A_A") (pintype "passive"))
      (node (ref "RN2") (pin "5") (pinfunction "2_5") (pintype "passive"))
    )
    (net (code "79") (name "unconnected-(GND-*D3-Pad3)") (class "Default")
      (node (ref "GND") (pin "3") (pinfunction "*D3_3") (pintype "bidirectional"))
    )
    (net (code "80") (name "unconnected-(GND-*D5-Pad5)") (class "Default")
      (node (ref "GND") (pin "5") (pinfunction "*D5_5") (pintype "bidirectional"))
    )
    (net (code "81") (name "unconnected-(GND-*D6-Pad6)") (class "Default")
      (node (ref "GND") (pin "6") (pinfunction "*D6_6") (pintype "bidirectional"))
    )
    (net (code "82") (name "unconnected-(GND-*D9-Pad9)") (class "Default")
      (node (ref "GND") (pin "9") (pinfunction "*D9_9") (pintype "bidirectional"))
    )
    (net (code "83") (name "unconnected-(GND-*D10-Pad10)") (class "Default")
      (node (ref "GND") (pin "10") (pinfunction "*D10_10") (pintype "bidirectional"))
    )
    (net (code "84") (name "unconnected-(GND-*D11-Pad11)") (class "Default")
      (node (ref "GND") (pin "11") (pinfunction "*D11_11") (pintype "bidirectional"))
    )
    (net (code "85") (name "unconnected-(GND-D2-Pad2)") (class "Default")
      (node (ref "GND") (pin "2") (pinfunction "D2_2") (pintype "bidirectional"))
    )
    (net (code "86") (name "unconnected-(GND-D4-Pad4)") (class "Default")
      (node (ref "GND") (pin "4") (pinfunction "D4_4") (pintype "bidirectional"))
    )
    (net (code "87") (name "unconnected-(GND-D7-Pad7)") (class "Default")
      (node (ref "GND") (pin "7") (pinfunction "D7_7") (pintype "bidirectional"))
    )
    (net (code "88") (name "unconnected-(GND-D8-Pad8)") (class "Default")
      (node (ref "GND") (pin "8") (pinfunction "D8_8") (pintype "bidirectional"))
    )
    (net (code "89") (name "unconnected-(GND-D12-Pad12)") (class "Default")
      (node (ref "GND") (pin "12") (pinfunction "D12_12") (pintype "bidirectional"))
    )
    (net (code "90") (name "unconnected-(GND-D13-Pad13)") (class "Default")
      (node (ref "GND") (pin "13") (pinfunction "D13_13") (pintype "bidirectional"))
    )
    (net (code "91") (name "unconnected-(GND-Pad3.3V)") (class "Default")
      (node (ref "GND") (pin "3.3V") (pinfunction "3.3V_3.3V") (pintype "bidirectional"))
    )
    (net (code "92") (name "unconnected-(GND-PadA0)") (class "Default")
      (node (ref "GND") (pin "A0") (pinfunction "A0_A0") (pintype "bidirectional"))
    )
    (net (code "93") (name "unconnected-(GND-PadA1)") (class "Default")
      (node (ref "GND") (pin "A1") (pinfunction "A1_A1") (pintype "bidirectional"))
    )
    (net (code "94") (name "unconnected-(GND-PadA2)") (class "Default")
      (node (ref "GND") (pin "A2") (pinfunction "A2_A2") (pintype "bidirectional"))
    )
    (net (code "95") (name "unconnected-(GND-PadA3)") (class "Default")
      (node (ref "GND") (pin "A3") (pinfunction "A3_A3") (pintype "bidirectional"))
    )
    (net (code "96") (name "unconnected-(GND-PadAREF)") (class "Default")
      (node (ref "GND") (pin "AREF") (pinfunction "AREF_AREF") (pintype "bidirectional"))
    )
    (net (code "97") (name "unconnected-(GND-RX-Pad0)") (class "Default")
      (node (ref "GND") (pin "0") (pinfunction "RX_0") (pintype "bidirectional"))
    )
    (net (code "98") (name "unconnected-(GND-TX-Pad1)") (class "Default")
      (node (ref "GND") (pin "1") (pinfunction "TX_1") (pintype "bidirectional"))
    )
    (net (code "99") (name "unconnected-(IC2-INTA-Pad20)") (class "Default")
      (node (ref "IC2") (pin "20") (pinfunction "INTA_20") (pintype "output"))
    )
    (net (code "100") (name "unconnected-(IC2-INTB-Pad19)") (class "Default")
      (node (ref "IC2") (pin "19") (pinfunction "INTB_19") (pintype "output"))
    )
    (net (code "101") (name "unconnected-(K1B-O-PadO1)") (class "Default")
      (node (ref "K1") (pin "O1") (pinfunction "O_O1") (pintype "passive"))
    )
    (net (code "102") (name "unconnected-(K1C-O-PadO2)") (class "Default")
      (node (ref "K1") (pin "O2") (pinfunction "O_O2") (pintype "passive"))
    )
    (net (code "103") (name "unconnected-(K2B-O-PadO1)") (class "Default")
      (node (ref "K2") (pin "O1") (pinfunction "O_O1") (pintype "passive"))
    )
    (net (code "104") (name "unconnected-(K2C-O-PadO2)") (class "Default")
      (node (ref "K2") (pin "O2") (pinfunction "O_O2") (pintype "passive"))
    )
    (net (code "105") (name "unconnected-(K3B-O-PadO1)") (class "Default")
      (node (ref "K3") (pin "O1") (pinfunction "O_O1") (pintype "passive"))
    )
    (net (code "106") (name "unconnected-(K3C-O-PadO2)") (class "Default")
      (node (ref "K3") (pin "O2") (pinfunction "O_O2") (pintype "passive"))
    )
    (net (code "107") (name "unconnected-(K4B-O-PadO1)") (class "Default")
      (node (ref "K4") (pin "O1") (pinfunction "O_O1") (pintype "passive"))
    )
    (net (code "108") (name "unconnected-(K4C-O-PadO2)") (class "Default")
      (node (ref "K4") (pin "O2") (pinfunction "O_O2") (pintype "passive"))
    )
    (net (code "109") (name "unconnected-(K5B-O-PadO1)") (class "Default")
      (node (ref "K5") (pin "O1") (pinfunction "O_O1") (pintype "passive"))
    )
    (net (code "110") (name "unconnected-(K5C-O-PadO2)") (class "Default")
      (node (ref "K5") (pin "O2") (pinfunction "O_O2") (pintype "passive"))
    )
    (net (code "111") (name "unconnected-(K6B-O-PadO1)") (class "Default")
      (node (ref "K6") (pin "O1") (pinfunction "O_O1") (pintype "passive"))
    )
    (net (code "112") (name "unconnected-(K6C-O-PadO2)") (class "Default")
      (node (ref "K6") (pin "O2") (pinfunction "O_O2") (pintype "passive"))
    )
    (net (code "113") (name "unconnected-(K7B-O-PadO1)") (class "Default")
      (node (ref "K7") (pin "O1") (pinfunction "O_O1") (pintype "passive"))
    )
    (net (code "114") (name "unconnected-(K7C-O-PadO2)") (class "Default")
      (node (ref "K7") (pin "O2") (pinfunction "O_O2") (pintype "passive"))
    )
    (net (code "115") (name "unconnected-(K8B-O-PadO1)") (class "Default")
      (node (ref "K8") (pin "O1") (pinfunction "O_O1") (pintype "passive"))
    )
    (net (code "116") (name "unconnected-(K8C-O-PadO2)") (class "Default")
      (node (ref "K8") (pin "O2") (pinfunction "O_O2") (pintype "passive"))
    )
    (net (code "117") (name "unconnected-(RN7A-2-Pad8)") (class "Default")
      (node (ref "RN7") (pin "8") (pinfunction "2_8") (pintype "passive"))
    )
    (net (code "118") (name "unconnected-(SERIAL-Pad5)") (class "Default")
      (node (ref "SERIAL") (pin "5") (pinfunction "5_5") (pintype "passive"))
    )
    (net (code "119") (name "unconnected-(SERIAL-Pad6)") (class "Default")
      (node (ref "SERIAL") (pin "6") (pinfunction "6_6") (pintype "passive"))
    )
    (net (code "120") (name "unconnected-(SERIAL-Pad7)") (class "Default")
      (node (ref "SERIAL") (pin "7") (pinfunction "7_7") (pintype "passive"))
    )
    (net (code "121") (name "unconnected-(SERIAL-Pad8)") (class "Default")
      (node (ref "SERIAL") (pin "8") (pinfunction "8_8") (pintype "passive"))
    )
  )
)
